# EVENTCTRL_CAL.net
KiCad netlist of a schematic drawn in Altium Designer
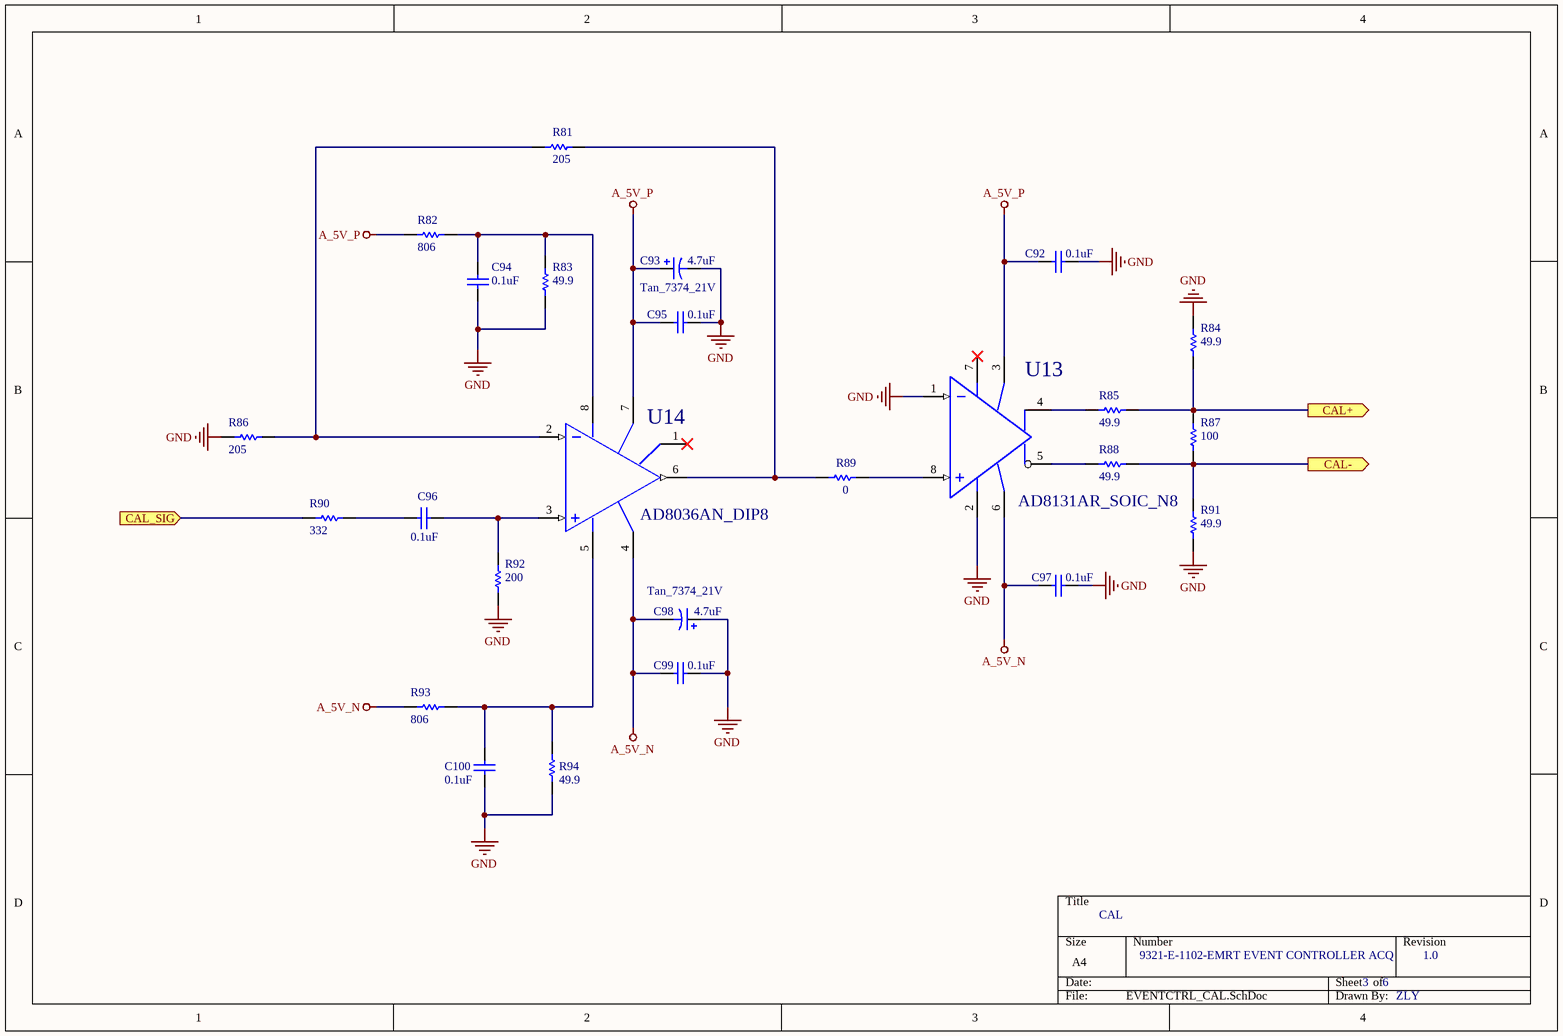
[diagram p0: EVENTCTRL_CAL.SchDoc]

(export (version "E")
  (design (tool "Eeschema 10.0.6"))
  (components
    (comp (ref "C92")
      (value "0.1uF")
      (footprint "0805")
      (description "Capacitor")
      (fields (field (name "Comment") "C0805"))
      (libsource (lib "Miscellaneous Devices") (part "Cap"))
    )
    (comp (ref "C93")
      (value "Tan_7374_21V")
      (footprint "7343")
      (description "Polarized Capacitor (Radial)")
      (fields (field (name "ALTIUM_VALUE") "4.7uF"))
      (libsource (lib "Miscellaneous Devices") (part "Cap Pol1"))
    )
    (comp (ref "C94")
      (value "0.1uF")
      (footprint "0805")
      (description "Capacitor")
      (fields (field (name "Comment") "C0805"))
      (libsource (lib "Miscellaneous Devices") (part "Cap"))
    )
    (comp (ref "C95")
      (value "0.1uF")
      (footprint "0805")
      (description "Capacitor")
      (fields (field (name "Comment") "C0805"))
      (libsource (lib "Miscellaneous Devices") (part "Cap"))
    )
    (comp (ref "C96")
      (value "0.1uF")
      (footprint "0805")
      (description "Capacitor")
      (fields (field (name "Comment") "C0805"))
      (libsource (lib "Miscellaneous Devices") (part "Cap"))
    )
    (comp (ref "C97")
      (value "0.1uF")
      (footprint "0805")
      (description "Capacitor")
      (fields (field (name "Comment") "C0805"))
      (libsource (lib "Miscellaneous Devices") (part "Cap"))
    )
    (comp (ref "C98")
      (value "Tan_7374_21V")
      (footprint "7343")
      (description "Polarized Capacitor (Radial)")
      (fields (field (name "ALTIUM_VALUE") "4.7uF"))
      (libsource (lib "Miscellaneous Devices") (part "Cap Pol1"))
    )
    (comp (ref "C99")
      (value "0.1uF")
      (footprint "0805")
      (description "Capacitor")
      (fields (field (name "Comment") "C0805"))
      (libsource (lib "Miscellaneous Devices") (part "Cap"))
    )
    (comp (ref "C100")
      (value "0.1uF")
      (footprint "0805")
      (description "Capacitor")
      (fields (field (name "Comment") "C0805"))
      (libsource (lib "Miscellaneous Devices") (part "Cap"))
    )
    (comp (ref "R81")
      (value "205")
      (footprint "R0805")
      (description "Resistor")
      (fields (field (name "Comment") "R0805"))
      (libsource (lib "Miscellaneous Devices") (part "Res1"))
    )
    (comp (ref "R82")
      (value "806")
      (footprint "R0805")
      (description "Resistor")
      (fields (field (name "Comment") "R0805"))
      (libsource (lib "Miscellaneous Devices") (part "Res1"))
    )
    (comp (ref "R83")
      (value "49.9")
      (footprint "R0805")
      (description "Resistor")
      (fields (field (name "Comment") "R0805"))
      (libsource (lib "Miscellaneous Devices") (part "Res1"))
    )
    (comp (ref "R84")
      (value "49.9")
      (footprint "R0805")
      (description "Resistor")
      (fields (field (name "Comment") "R0805"))
      (libsource (lib "Miscellaneous Devices") (part "Res1"))
    )
    (comp (ref "R85")
      (value "49.9")
      (footprint "R0805")
      (description "Resistor")
      (fields (field (name "Comment") "R0805"))
      (libsource (lib "Miscellaneous Devices") (part "Res1"))
    )
    (comp (ref "R86")
      (value "205")
      (footprint "R0805")
      (description "Resistor")
      (fields (field (name "Comment") "R0805"))
      (libsource (lib "Miscellaneous Devices") (part "Res1"))
    )
    (comp (ref "R87")
      (value "100")
      (footprint "R0805")
      (description "Resistor")
      (fields (field (name "Comment") "R0805"))
      (libsource (lib "Miscellaneous Devices") (part "Res1"))
    )
    (comp (ref "R88")
      (value "49.9")
      (footprint "R0805")
      (description "Resistor")
      (fields (field (name "Comment") "R0805"))
      (libsource (lib "Miscellaneous Devices") (part "Res1"))
    )
    (comp (ref "R89")
      (value "0")
      (footprint "R0805")
      (description "Resistor")
      (fields (field (name "Comment") "R0805"))
      (libsource (lib "Miscellaneous Devices") (part "Res1"))
    )
    (comp (ref "R90")
      (value "332")
      (footprint "R0805")
      (description "Resistor")
      (fields (field (name "Comment") "R0805"))
      (libsource (lib "Miscellaneous Devices") (part "Res1"))
    )
    (comp (ref "R91")
      (value "49.9")
      (footprint "R0805")
      (description "Resistor")
      (fields (field (name "Comment") "R0805"))
      (libsource (lib "Miscellaneous Devices") (part "Res1"))
    )
    (comp (ref "R92")
      (value "200")
      (footprint "R0805")
      (description "Resistor")
      (fields (field (name "Comment") "R0805"))
      (libsource (lib "Miscellaneous Devices") (part "Res1"))
    )
    (comp (ref "R93")
      (value "806")
      (footprint "R0805")
      (description "Resistor")
      (fields (field (name "Comment") "R0805"))
      (libsource (lib "Miscellaneous Devices") (part "Res1"))
    )
    (comp (ref "R94")
      (value "49.9")
      (footprint "R0805")
      (description "Resistor")
      (fields (field (name "Comment") "R0805"))
      (libsource (lib "Miscellaneous Devices") (part "Res1"))
    )
    (comp (ref "U13") (value "AD8131AR_SOIC_N8") (footprint "SO-8") (libsource (lib "*") (part "AD8131AR")))
    (comp (ref "U14") (value "AD8036AN_DIP8") (footprint "DIP8") (libsource (lib "srj") (part "AD8036AN")))
  )
  (nets
    (net (code "1") (name "/CAL+") (class "Default")
      (node (ref "R84") (pin "1") (pinfunction "1_1") (pintype "passive"))
      (node (ref "R85") (pin "2") (pinfunction "2_2") (pintype "passive"))
      (node (ref "R87") (pin "2") (pinfunction "2_2") (pintype "passive"))
    )
    (net (code "2") (name "/CAL-") (class "Default")
      (node (ref "R87") (pin "1") (pinfunction "1_1") (pintype "passive"))
      (node (ref "R88") (pin "2") (pinfunction "2_2") (pintype "passive"))
      (node (ref "R91") (pin "2") (pinfunction "2_2") (pintype "passive"))
    )
    (net (code "3") (name "/CAL_SIG") (class "Default")
      (node (ref "R90") (pin "1") (pinfunction "1_1") (pintype "passive"))
    )
    (net (code "4") (name "A_5V_N") (class "Default")
      (node (ref "C97") (pin "1") (pinfunction "1_1") (pintype "passive"))
      (node (ref "C98") (pin "2") (pinfunction "2_2") (pintype "passive"))
      (node (ref "C99") (pin "1") (pinfunction "1_1") (pintype "passive"))
      (node (ref "R93") (pin "1") (pinfunction "1_1") (pintype "passive"))
      (node (ref "U13") (pin "6") (pinfunction "V-_6") (pintype "power_in"))
      (node (ref "U14") (pin "4") (pinfunction "V-_4") (pintype "power_in"))
    )
    (net (code "5") (name "A_5V_P") (class "Default")
      (node (ref "C92") (pin "1") (pinfunction "1_1") (pintype "passive"))
      (node (ref "C93") (pin "1") (pinfunction "1_1") (pintype "passive"))
      (node (ref "C95") (pin "1") (pinfunction "1_1") (pintype "passive"))
      (node (ref "R82") (pin "1") (pinfunction "1_1") (pintype "passive"))
      (node (ref "U13") (pin "3") (pinfunction "V+_3") (pintype "power_in"))
      (node (ref "U14") (pin "7") (pinfunction "V+_7") (pintype "power_in"))
    )
    (net (code "6") (name "GND") (class "Default")
      (node (ref "C100") (pin "1") (pinfunction "1_1") (pintype "passive"))
      (node (ref "C92") (pin "2") (pinfunction "2_2") (pintype "passive"))
      (node (ref "C93") (pin "2") (pinfunction "2_2") (pintype "passive"))
      (node (ref "C94") (pin "1") (pinfunction "1_1") (pintype "passive"))
      (node (ref "C95") (pin "2") (pinfunction "2_2") (pintype "passive"))
      (node (ref "C97") (pin "2") (pinfunction "2_2") (pintype "passive"))
      (node (ref "C98") (pin "1") (pinfunction "1_1") (pintype "passive"))
      (node (ref "C99") (pin "2") (pinfunction "2_2") (pintype "passive"))
      (node (ref "R83") (pin "1") (pinfunction "1_1") (pintype "passive"))
      (node (ref "R84") (pin "2") (pinfunction "2_2") (pintype "passive"))
      (node (ref "R86") (pin "1") (pinfunction "1_1") (pintype "passive"))
      (node (ref "R91") (pin "1") (pinfunction "1_1") (pintype "passive"))
      (node (ref "R92") (pin "1") (pinfunction "1_1") (pintype "passive"))
      (node (ref "R94") (pin "1") (pinfunction "1_1") (pintype "passive"))
      (node (ref "U13") (pin "1") (pinfunction "Din-_1") (pintype "input"))
      (node (ref "U13") (pin "2") (pinfunction "Vcom_2") (pintype "passive"))
    )
    (net (code "7") (name "Net-(C94-Pad2)") (class "Default")
      (node (ref "C94") (pin "2") (pinfunction "2_2") (pintype "passive"))
      (node (ref "R82") (pin "2") (pinfunction "2_2") (pintype "passive"))
      (node (ref "R83") (pin "2") (pinfunction "2_2") (pintype "passive"))
      (node (ref "U14") (pin "8") (pinfunction "V+_8") (pintype "power_in"))
    )
    (net (code "8") (name "Net-(C96-Pad1)") (class "Default")
      (node (ref "C96") (pin "1") (pinfunction "1_1") (pintype "passive"))
      (node (ref "R90") (pin "2") (pinfunction "2_2") (pintype "passive"))
    )
    (net (code "9") (name "Net-(C100-Pad2)") (class "Default")
      (node (ref "C100") (pin "2") (pinfunction "2_2") (pintype "passive"))
      (node (ref "R93") (pin "2") (pinfunction "2_2") (pintype "passive"))
      (node (ref "R94") (pin "2") (pinfunction "2_2") (pintype "passive"))
      (node (ref "U14") (pin "5") (pinfunction "V-_5") (pintype "power_in"))
    )
    (net (code "10") (name "Net-(U13-Din+)") (class "Default")
      (node (ref "R89") (pin "2") (pinfunction "2_2") (pintype "passive"))
      (node (ref "U13") (pin "8") (pinfunction "Din+_8") (pintype "input"))
    )
    (net (code "11") (name "Net-(U13-OUT+)") (class "Default")
      (node (ref "R85") (pin "1") (pinfunction "1_1") (pintype "passive"))
      (node (ref "U13") (pin "4") (pinfunction "OUT+_4") (pintype "passive"))
    )
    (net (code "12") (name "Net-(U13-OUT-)") (class "Default")
      (node (ref "R88") (pin "1") (pinfunction "1_1") (pintype "passive"))
      (node (ref "U13") (pin "5") (pinfunction "OUT-_5") (pintype "passive"))
    )
    (net (code "13") (name "Net-(U14-IN+)") (class "Default")
      (node (ref "C96") (pin "2") (pinfunction "2_2") (pintype "passive"))
      (node (ref "R92") (pin "2") (pinfunction "2_2") (pintype "passive"))
      (node (ref "U14") (pin "3") (pinfunction "IN+_3") (pintype "input"))
    )
    (net (code "14") (name "Net-(U14-IN-)") (class "Default")
      (node (ref "R81") (pin "1") (pinfunction "1_1") (pintype "passive"))
      (node (ref "R86") (pin "2") (pinfunction "2_2") (pintype "passive"))
      (node (ref "U14") (pin "2") (pinfunction "IN-_2") (pintype "input"))
    )
    (net (code "15") (name "Net-(U14-OUT)") (class "Default")
      (node (ref "R81") (pin "2") (pinfunction "2_2") (pintype "passive"))
      (node (ref "R89") (pin "1") (pinfunction "1_1") (pintype "passive"))
      (node (ref "U14") (pin "6") (pinfunction "OUT_6") (pintype "output"))
    )
    (net (code "16") (name "unconnected-(U13-NC-Pad7)") (class "Default")
      (node (ref "U13") (pin "7") (pinfunction "NC_7") (pintype "passive+no_connect"))
    )
    (net (code "17") (name "unconnected-(U14-NC-Pad1)") (class "Default")
      (node (ref "U14") (pin "1") (pinfunction "NC_1") (pintype "passive+no_connect"))
    )
  )
)
